# DFN1X1.net
KiCad netlist of a schematic drawn in Altium Designer
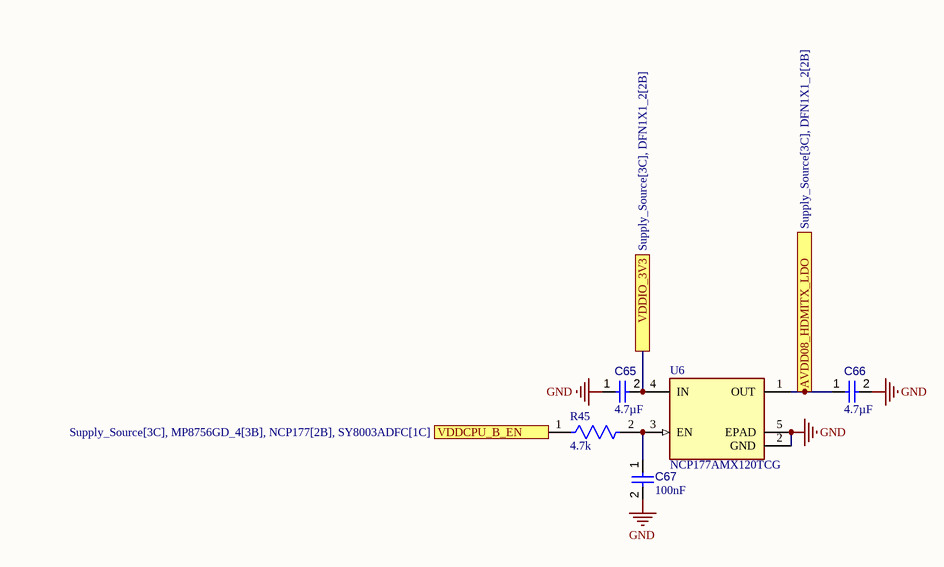
[diagram p0: DFN1X1.SchDoc]

(export (version "E")
  (design (tool "Eeschema 10.0.6"))
  (components
    (comp (ref "C65")
      (value "4.7µF")
      (footprint "CAPC0603(1608)100_L")
      (description "Chip Capacitor, 4.7µF +/-20%, 10V, 0603, Thickness 1 mm")
      (fields (field (name "TOLERANCE") "10%") (field (name "Comment") "Capacitor 4.7µF +/-20% 10V 0603"))
      (libsource (lib "MIGUEL ANGEL ALVAREZ GUZMAN") (part "CAP-NP-2"))
    )
    (comp (ref "C66")
      (value "4.7µF")
      (footprint "CAPC0603(1608)100_L")
      (description "Chip Capacitor, 4.7µF +/-20%, 10V, 0603, Thickness 1 mm")
      (fields (field (name "TOLERANCE") "10%") (field (name "Comment") "Capacitor 4.7µF +/-20% 10V 0603"))
      (libsource (lib "MIGUEL ANGEL ALVAREZ GUZMAN") (part "CAP-NP-2"))
    )
    (comp (ref "C67")
      (value "100nF")
      (footprint "CAPC1005X56X25LL10T15")
      (description "Chip Capacitor, 0.1 uF, +/- 5%, 16 V, 0402 (1005 Metric)")
      (fields (field (name "TOLERANCE") "5%") (field (name "Comment") "Capacitor 0.1 uF +/- 5% 16 V 0402"))
      (libsource (lib "MIGUEL ANGEL ALVAREZ GUZMAN") (part "CAP-NP-2"))
    )
    (comp (ref "R45")
      (value "4.7k")
      (footprint "FP-RMCF0201-IPC_A")
      (description "Res Thick Film 0201 4.7K Ohm 5% 0.05W(1/20W) ±200ppm/C Pad SMD Automotive T/R")
      (fields (field (name "TOLERANCE") "5%") (field (name "Comment") "RMCF0201JT4K70"))
      (libsource (lib "MIGUEL ANGEL ALVAREZ GUZMAN") (part "1029c3af85768c4190bb7ad29bc67b5"))
    )
    (comp (ref "U6")
      (value "NCP177AMX120TCG")
      (footprint "FP-711AJ-MFG")
      (description "IC REG LINEAR 1.2V 500MA 4XDFN")
      (fields
        (field (name "OCTOPART") "https://octopart.com/ncp177amx120tcg-on+semiconductor-67320276")
        (field (name "MANUFACTURER") "ON Semiconductor")
      )
      (libsource (lib "Altium Content Vault") (part "8ad8dfd97c3e3b1b30caf0b800727eb"))
    )
  )
  (nets
    (net (code "1") (name "/AVDD08_HDMITX_LDO") (class "Default")
      (node (ref "C66") (pin "1") (pinfunction "1_1") (pintype "passive"))
      (node (ref "U6") (pin "1") (pinfunction "OUT_1") (pintype "power_in"))
    )
    (net (code "2") (name "/VDDCPU_B_EN") (class "Default")
      (node (ref "R45") (pin "1") (pinfunction "1_1") (pintype "passive"))
    )
    (net (code "3") (name "/VDDIO_3V3") (class "Default")
      (node (ref "C65") (pin "2") (pinfunction "2_2") (pintype "passive"))
      (node (ref "U6") (pin "4") (pinfunction "IN_4") (pintype "power_in"))
    )
    (net (code "4") (name "GND") (class "Default")
      (node (ref "C65") (pin "1") (pinfunction "1_1") (pintype "passive"))
      (node (ref "C66") (pin "2") (pinfunction "2_2") (pintype "passive"))
      (node (ref "C67") (pin "2") (pinfunction "2_2") (pintype "passive"))
      (node (ref "U6") (pin "2") (pinfunction "GND_2") (pintype "power_in"))
      (node (ref "U6") (pin "5") (pinfunction "EPAD_5") (pintype "power_in"))
    )
    (net (code "5") (name "Net-(U6-EN)") (class "Default")
      (node (ref "C67") (pin "1") (pinfunction "1_1") (pintype "passive"))
      (node (ref "R45") (pin "2") (pinfunction "2_2") (pintype "passive"))
      (node (ref "U6") (pin "3") (pinfunction "EN_3") (pintype "input"))
    )
  )
)
